# ControlBoard.net
KiCad netlist of a schematic drawn in Altium Designer
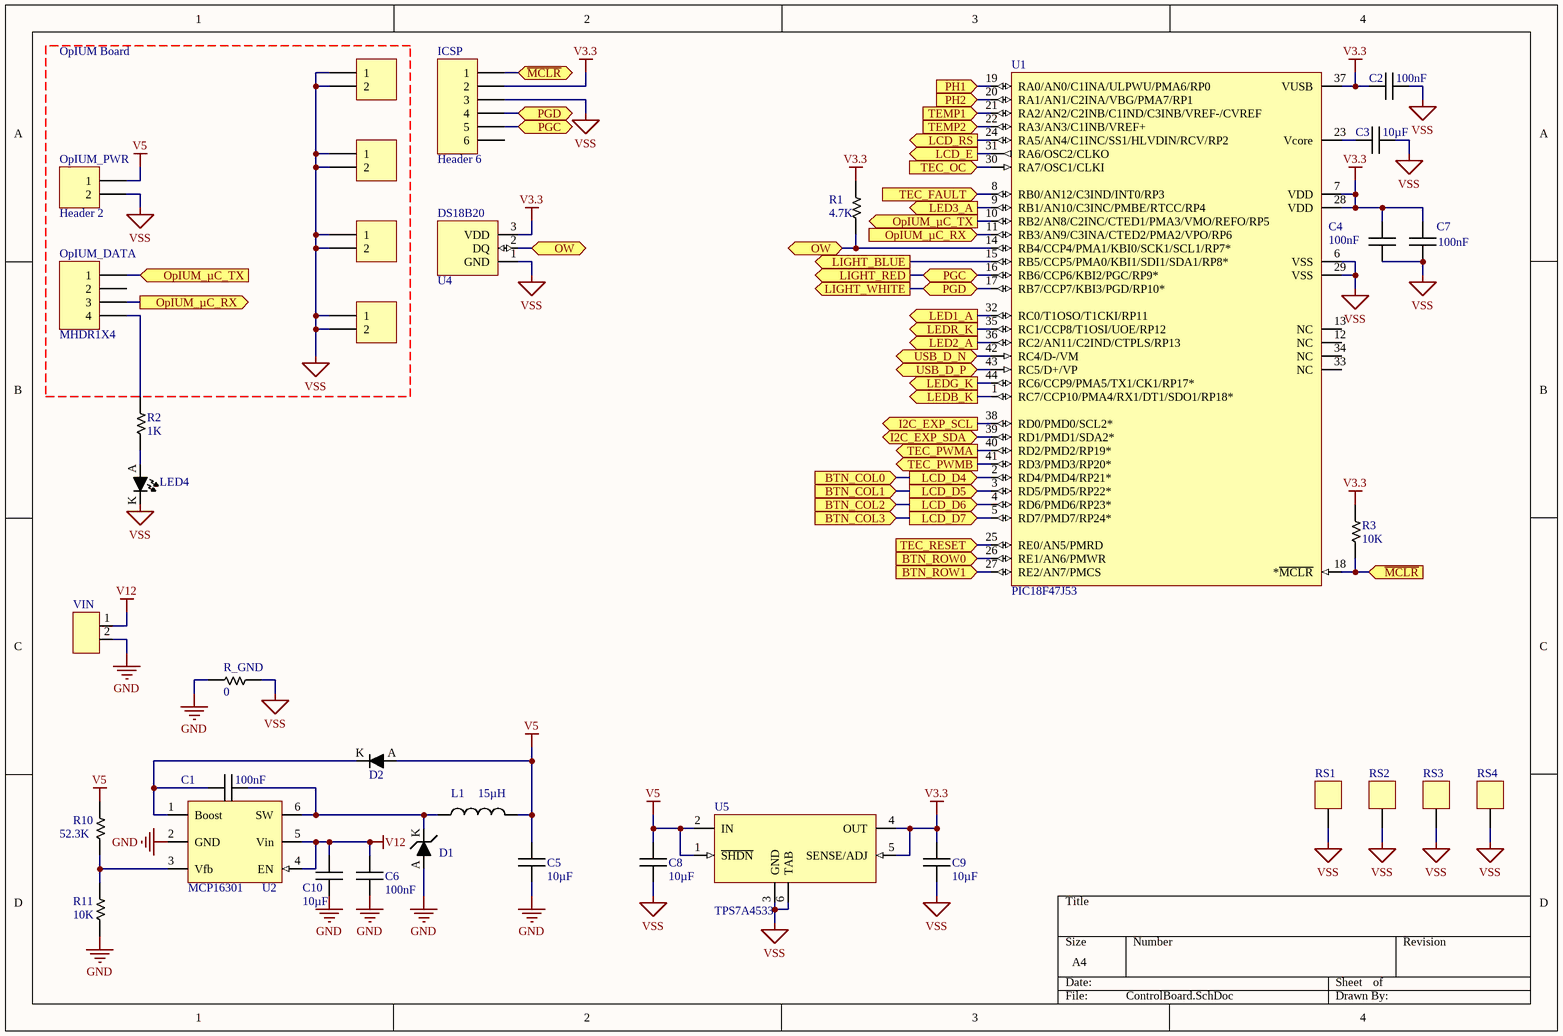
[diagram p0: ControlBoard.SchDoc]

(export (version "E")
  (design (tool "Eeschema 10.0.6"))
  (components
    (comp (ref "C1") (value "100nF") (footprint "CAPC1608N") (libsource (lib "Megaxone") (part "Capacitor")))
    (comp (ref "C2") (value "100nF") (footprint "CAPC1608N") (libsource (lib "Megaxone") (part "Capacitor")))
    (comp (ref "C3") (value "10µF") (footprint "CAPC2012N") (libsource (lib "Megaxone") (part "Capacitor")))
    (comp (ref "C4") (value "100nF") (footprint "CAPC1608N") (libsource (lib "Megaxone") (part "Capacitor")))
    (comp (ref "C5") (value "10µF") (footprint "CAPC2012N") (libsource (lib "Megaxone") (part "Capacitor")))
    (comp (ref "C6") (value "100nF") (footprint "CAPC1608N") (libsource (lib "Megaxone") (part "Capacitor")))
    (comp (ref "C7") (value "100nF") (footprint "CAPC1608N") (libsource (lib "Megaxone") (part "Capacitor")))
    (comp (ref "C8") (value "10µF") (footprint "CAPC2012N") (libsource (lib "Megaxone") (part "Capacitor")))
    (comp (ref "C9") (value "10µF") (footprint "CAPC2012N") (libsource (lib "Megaxone") (part "Capacitor")))
    (comp (ref "C10") (value "10µF") (footprint "CAPC3225N") (libsource (lib "Megaxone") (part "Capacitor")))
    (comp (ref "D1")
      (value "Schottky Diode")
      (footprint "DO-214AC")
      (libsource (lib "Megaxone") (part "Schottky Diode"))
    )
    (comp (ref "D2") (value "Diode") (footprint "SOT323") (libsource (lib "Megaxone") (part "Diode")))
    (comp (ref "ICSP")
      (value "Header 6")
      (footprint "HDR1X6")
      (description "Header, 6-Pin")
      (fields (field (name "PUBLISHER") "Altium Limited"))
      (libsource (lib "Miscellaneous Connectors") (part "Header 6"))
    )
    (comp (ref "L1")
      (value "15µH")
      (footprint "INDUCTOR 6×6mm Taiyo Yuden")
      (libsource (lib "Megaxone") (part "Inductor"))
    )
    (comp (ref "LED4") (value "~") (footprint "LED 1608m") (libsource (lib "Megaxone") (part "LED")))
    (comp (ref "OpIUM_DATA")
      (value "MHDR1X4")
      (footprint "MHDR1X4")
      (description "Header, 4-Pin")
      (fields (field (name "PUBLISHER") "Altium Limited"))
      (libsource (lib "Miscellaneous Connectors") (part "MHDR1X4"))
    )
    (comp (ref "OpIUM_PWR")
      (value "Header 2")
      (footprint "HDR1X2")
      (description "Header, 2-Pin")
      (fields (field (name "PUBLISHER") "Altium Limited"))
      (libsource (lib "Miscellaneous Connectors") (part "Header 2"))
    )
    (comp (ref "R1") (value "4.7K") (footprint "RESC1608N") (libsource (lib "Megaxone") (part "Resistor")))
    (comp (ref "R2") (value "1K") (footprint "RESC1608N") (libsource (lib "Megaxone") (part "Resistor")))
    (comp (ref "R3") (value "10K") (footprint "RESC1608N") (libsource (lib "Megaxone") (part "Resistor")))
    (comp (ref "R10") (value "52.3K") (footprint "RESC1608N") (libsource (lib "Megaxone") (part "Resistor")))
    (comp (ref "R11") (value "10K") (footprint "RESC1608N") (libsource (lib "Megaxone") (part "Resistor")))
    (comp (ref "RS1")
      (value "PCB Riser")
      (footprint "PCB Riser 6×10mm 3mm")
      (libsource (lib "Megaxone") (part "PCB Riser"))
    )
    (comp (ref "RS2")
      (value "PCB Riser")
      (footprint "PCB Riser 6×10mm 3mm")
      (libsource (lib "Megaxone") (part "PCB Riser"))
    )
    (comp (ref "RS3")
      (value "PCB Riser")
      (footprint "PCB Riser 6×10mm 3mm")
      (libsource (lib "Megaxone") (part "PCB Riser"))
    )
    (comp (ref "RS4")
      (value "PCB Riser")
      (footprint "PCB Riser 6×10mm 3mm")
      (libsource (lib "Megaxone") (part "PCB Riser"))
    )
    (comp (ref "R_GND") (value "0") (footprint "RESC1608N") (libsource (lib "") (part "Resistor_1")))
    (comp (ref "SUPPORT1")
      (value "MHDR1X2")
      (footprint "MHDR1X2")
      (description "Header, 2-Pin")
      (fields (field (name "PUBLISHER") "Altium Limited"))
      (libsource (lib "Miscellaneous Connectors") (part "MHDR1X2"))
    )
    (comp (ref "SUPPORT2")
      (value "MHDR1X2")
      (footprint "MHDR1X2")
      (description "Header, 2-Pin")
      (fields (field (name "PUBLISHER") "Altium Limited"))
      (libsource (lib "Miscellaneous Connectors") (part "MHDR1X2"))
    )
    (comp (ref "SUPPORT3")
      (value "MHDR1X2")
      (footprint "MHDR1X2")
      (description "Header, 2-Pin")
      (fields (field (name "PUBLISHER") "Altium Limited"))
      (libsource (lib "Miscellaneous Connectors") (part "MHDR1X2"))
    )
    (comp (ref "SUPPORT4")
      (value "MHDR1X2")
      (footprint "MHDR1X2")
      (description "Header, 2-Pin")
      (fields (field (name "PUBLISHER") "Altium Limited"))
      (libsource (lib "Miscellaneous Connectors") (part "MHDR1X2"))
    )
    (comp (ref "U1")
      (value "PIC18F47J53")
      (footprint "TQFP-PT44_N")
      (libsource (lib "Megaxone") (part "PIC18F47J53"))
    )
    (comp (ref "U2")
      (value "MCP16301")
      (footprint "SOT23-6_N")
      (libsource (lib "Megaxone") (part "MCP16301"))
    )
    (comp (ref "U4") (value "DS18B20") (footprint "TO-92A") (libsource (lib "Megaxone") (part "DS18B20")))
    (comp (ref "U5")
      (value "TPS7A4533")
      (footprint "SOT223-6N")
      (libsource (lib "Megaxone") (part "TPS7A45xx"))
    )
    (comp (ref "VIN")
      (value "High-Power Connector 2p")
      (footprint "High-Power Connector 2")
      (libsource (lib "Megaxone") (part "High-Power Connector 2p"))
    )
  )
  (nets
    (net (code "1") (name "/BTN_COL0") (class "Default")
      (node (ref "U1") (pin "2") (pinfunction "RD4/PMD4/RP21*_2") (pintype "bidirectional"))
    )
    (net (code "2") (name "/BTN_COL1") (class "Default")
      (node (ref "U1") (pin "3") (pinfunction "RD5/PMD5/RP22*_3") (pintype "bidirectional"))
    )
    (net (code "3") (name "/BTN_COL2") (class "Default")
      (node (ref "U1") (pin "4") (pinfunction "RD6/PMD6/RP23*_4") (pintype "bidirectional"))
    )
    (net (code "4") (name "/BTN_COL3") (class "Default")
      (node (ref "U1") (pin "5") (pinfunction "RD7/PMD7/RP24*_5") (pintype "bidirectional"))
    )
    (net (code "5") (name "/BTN_ROW0") (class "Default")
      (node (ref "U1") (pin "26") (pinfunction "RE1/AN6/PMWR_26") (pintype "bidirectional"))
    )
    (net (code "6") (name "/BTN_ROW1") (class "Default")
      (node (ref "U1") (pin "27") (pinfunction "RE2/AN7/PMCS_27") (pintype "bidirectional"))
    )
    (net (code "7") (name "/I2C_EXP_SCL") (class "Default")
      (node (ref "U1") (pin "38") (pinfunction "RD0/PMD0/SCL2*_38") (pintype "bidirectional"))
    )
    (net (code "8") (name "/I2C_EXP_SDA") (class "Default")
      (node (ref "U1") (pin "39") (pinfunction "RD1/PMD1/SDA2*_39") (pintype "bidirectional"))
    )
    (net (code "9") (name "/LCD_E") (class "Default")
      (node (ref "U1") (pin "31") (pinfunction "RA6/OSC2/CLKO_31") (pintype "output"))
    )
    (net (code "10") (name "/LCD_RS") (class "Default")
      (node (ref "U1") (pin "24") (pinfunction "RA5/AN4/C1INC/SS1/HLVDIN/RCV/RP2_24") (pintype "bidirectional"))
    )
    (net (code "11") (name "/LED1_A") (class "Default")
      (node (ref "U1") (pin "32") (pinfunction "RC0/T1OSO/T1CKI/RP11_32") (pintype "bidirectional"))
    )
    (net (code "12") (name "/LED2_A") (class "Default")
      (node (ref "U1") (pin "36") (pinfunction "RC2/AN11/C2IND/CTPLS/RP13_36") (pintype "bidirectional"))
    )
    (net (code "13") (name "/LED3_A") (class "Default")
      (node (ref "U1") (pin "9") (pinfunction "RB1/AN10/C3INC/PMBE/RTCC/RP4_9") (pintype "bidirectional"))
    )
    (net (code "14") (name "/LEDB_K") (class "Default")
      (node (ref "U1") (pin "1") (pinfunction "RC7/CCP10/PMA4/RX1/DT1/SDO1/RP18*_1") (pintype "bidirectional"))
    )
    (net (code "15") (name "/LEDG_K") (class "Default")
      (node (ref "U1") (pin "44") (pinfunction "RC6/CCP9/PMA5/TX1/CK1/RP17*_44") (pintype "bidirectional"))
    )
    (net (code "16") (name "/LEDR_K") (class "Default")
      (node (ref "U1") (pin "35") (pinfunction "RC1/CCP8/T1OSI/UOE/RP12_35") (pintype "bidirectional"))
    )
    (net (code "17") (name "/LIGHT_BLUE") (class "Default")
      (node (ref "U1") (pin "15") (pinfunction "RB5/CCP5/PMA0/KBI1/SDI1/SDA1/RP8*_15") (pintype "bidirectional"))
    )
    (net (code "18") (name "/LIGHT_RED") (class "Default")
      (node (ref "ICSP") (pin "5") (pinfunction "5_5") (pintype "passive"))
      (node (ref "U1") (pin "16") (pinfunction "RB6/CCP6/KBI2/PGC/RP9*_16") (pintype "bidirectional"))
    )
    (net (code "19") (name "/LIGHT_WHITE") (class "Default")
      (node (ref "ICSP") (pin "4") (pinfunction "4_4") (pintype "passive"))
      (node (ref "U1") (pin "17") (pinfunction "RB7/CCP7/KBI3/PGD/RP10*_17") (pintype "bidirectional"))
    )
    (net (code "20") (name "/OW") (class "Default")
      (node (ref "R1") (pin "1") (pinfunction "1_1") (pintype "passive"))
      (node (ref "U1") (pin "14") (pinfunction "RB4/CCP4/PMA1/KBI0/SCK1/SCL1/RP7*_14") (pintype "bidirectional"))
      (node (ref "U4") (pin "2") (pinfunction "DQ_2") (pintype "bidirectional"))
    )
    (net (code "21") (name "/OpIUM_µC_RX") (class "Default")
      (node (ref "OpIUM_DATA") (pin "3") (pinfunction "3_3") (pintype "passive"))
      (node (ref "U1") (pin "11") (pinfunction "RB3/AN9/C3INA/CTED2/PMA2/VPO/RP6_11") (pintype "bidirectional"))
    )
    (net (code "22") (name "/OpIUM_µC_TX") (class "Default")
      (node (ref "OpIUM_DATA") (pin "1") (pinfunction "1_1") (pintype "passive"))
      (node (ref "U1") (pin "10") (pinfunction "RB2/AN8/C2INC/CTED1/PMA3/VMO/REFO/RP5_10") (pintype "bidirectional"))
    )
    (net (code "23") (name "/PH1") (class "Default")
      (node (ref "U1") (pin "19") (pinfunction "RA0/AN0/C1INA/ULPWU/PMA6/RP0_19") (pintype "bidirectional"))
    )
    (net (code "24") (name "/PH2") (class "Default")
      (node (ref "U1") (pin "20") (pinfunction "RA1/AN1/C2INA/VBG/PMA7/RP1_20") (pintype "bidirectional"))
    )
    (net (code "25") (name "/TEC_FAULT") (class "Default")
      (node (ref "U1") (pin "8") (pinfunction "RB0/AN12/C3IND/INT0/RP3_8") (pintype "bidirectional"))
    )
    (net (code "26") (name "/TEC_OC") (class "Default")
      (node (ref "U1") (pin "30") (pinfunction "RA7/OSC1/CLKI_30") (pintype "input"))
    )
    (net (code "27") (name "/TEC_PWMA") (class "Default")
      (node (ref "U1") (pin "40") (pinfunction "RD2/PMD2/RP19*_40") (pintype "bidirectional"))
    )
    (net (code "28") (name "/TEC_PWMB") (class "Default")
      (node (ref "U1") (pin "41") (pinfunction "RD3/PMD3/RP20*_41") (pintype "bidirectional"))
    )
    (net (code "29") (name "/TEC_RESET") (class "Default")
      (node (ref "U1") (pin "25") (pinfunction "RE0/AN5/PMRD_25") (pintype "bidirectional"))
    )
    (net (code "30") (name "/TEMP1") (class "Default")
      (node (ref "U1") (pin "21") (pinfunction "RA2/AN2/C2INB/C1IND/C3INB/VREF-/CVREF_21") (pintype "bidirectional"))
    )
    (net (code "31") (name "/TEMP2") (class "Default")
      (node (ref "U1") (pin "22") (pinfunction "RA3/AN3/C1INB/VREF+_22") (pintype "bidirectional"))
    )
    (net (code "32") (name "/USB_D_N") (class "Default")
      (node (ref "U1") (pin "42") (pinfunction "RC4/D-/VM_42") (pintype "input"))
    )
    (net (code "33") (name "/USB_D_P") (class "Default")
      (node (ref "U1") (pin "43") (pinfunction "RC5/D+/VP_43") (pintype "input"))
    )
    (net (code "34") (name "/~{MCLR}") (class "Default")
      (node (ref "ICSP") (pin "1") (pinfunction "1_1") (pintype "passive"))
      (node (ref "R3") (pin "1") (pinfunction "1_1") (pintype "passive"))
      (node (ref "U1") (pin "18") (pinfunction "*~{MCLR}_18") (pintype "input"))
    )
    (net (code "35") (name "GND") (class "Default")
      (node (ref "C10") (pin "1") (pinfunction "1_1") (pintype "passive"))
      (node (ref "C5") (pin "1") (pinfunction "1_1") (pintype "passive"))
      (node (ref "C6") (pin "2") (pinfunction "2_2") (pintype "passive"))
      (node (ref "D1") (pin "A") (pinfunction "Anode_A") (pintype "power_in"))
      (node (ref "R11") (pin "1") (pinfunction "1_1") (pintype "passive"))
      (node (ref "R_GND") (pin "1") (pinfunction "1_1") (pintype "passive"))
      (node (ref "U2") (pin "2") (pinfunction "GND_2") (pintype "power_in"))
      (node (ref "VIN") (pin "2") (pinfunction "2_2") (pintype "power_in"))
    )
    (net (code "36") (name "Net-(D1-Kathode)") (class "Default")
      (node (ref "C1") (pin "1") (pinfunction "1_1") (pintype "passive"))
      (node (ref "D1") (pin "K") (pinfunction "Kathode_K") (pintype "power_in"))
      (node (ref "L1") (pin "1") (pinfunction "1_1") (pintype "passive"))
      (node (ref "U2") (pin "6") (pinfunction "SW_6") (pintype "power_in"))
    )
    (net (code "37") (name "Net-(LED4-PadA)") (class "Default")
      (node (ref "LED4") (pin "A") (pinfunction "A_A") (pintype "passive"))
      (node (ref "R2") (pin "1") (pinfunction "1_1") (pintype "passive"))
    )
    (net (code "38") (name "Net-(OpIUM_DATA-Pad4)") (class "Default")
      (node (ref "OpIUM_DATA") (pin "4") (pinfunction "4_4") (pintype "passive"))
      (node (ref "R2") (pin "2") (pinfunction "2_2") (pintype "passive"))
    )
    (net (code "39") (name "Net-(U1-Vcore)") (class "Default")
      (node (ref "C3") (pin "2") (pinfunction "2_2") (pintype "passive"))
      (node (ref "U1") (pin "23") (pinfunction "Vcore_23") (pintype "power_in"))
    )
    (net (code "40") (name "Net-(U2-Boost)") (class "Default")
      (node (ref "C1") (pin "2") (pinfunction "2_2") (pintype "passive"))
      (node (ref "D2") (pin "K") (pinfunction "K_K") (pintype "power_in"))
      (node (ref "U2") (pin "1") (pinfunction "Boost_1") (pintype "passive"))
    )
    (net (code "41") (name "Net-(U2-Vfb)") (class "Default")
      (node (ref "R10") (pin "1") (pinfunction "1_1") (pintype "passive"))
      (node (ref "R11") (pin "2") (pinfunction "2_2") (pintype "passive"))
      (node (ref "U2") (pin "3") (pinfunction "Vfb_3") (pintype "passive"))
    )
    (net (code "42") (name "V3.3") (class "Default")
      (node (ref "C2") (pin "2") (pinfunction "2_2") (pintype "passive"))
      (node (ref "C4") (pin "2") (pinfunction "2_2") (pintype "passive"))
      (node (ref "C7") (pin "2") (pinfunction "2_2") (pintype "passive"))
      (node (ref "C9") (pin "2") (pinfunction "2_2") (pintype "passive"))
      (node (ref "ICSP") (pin "2") (pinfunction "2_2") (pintype "passive"))
      (node (ref "R1") (pin "2") (pinfunction "2_2") (pintype "passive"))
      (node (ref "R3") (pin "2") (pinfunction "2_2") (pintype "passive"))
      (node (ref "U1") (pin "28") (pinfunction "VDD_28") (pintype "power_in"))
      (node (ref "U1") (pin "37") (pinfunction "VUSB_37") (pintype "power_in"))
      (node (ref "U1") (pin "7") (pinfunction "VDD_7") (pintype "power_in"))
      (node (ref "U4") (pin "3") (pinfunction "VDD_3") (pintype "power_in"))
      (node (ref "U5") (pin "4") (pinfunction "OUT_4") (pintype "power_in"))
      (node (ref "U5") (pin "5") (pinfunction "SENSE/ADJ_5") (pintype "input"))
    )
    (net (code "43") (name "V5") (class "Default")
      (node (ref "C5") (pin "2") (pinfunction "2_2") (pintype "passive"))
      (node (ref "C8") (pin "2") (pinfunction "2_2") (pintype "passive"))
      (node (ref "D2") (pin "A") (pinfunction "A_A") (pintype "power_in"))
      (node (ref "L1") (pin "2") (pinfunction "2_2") (pintype "passive"))
      (node (ref "OpIUM_PWR") (pin "1") (pinfunction "1_1") (pintype "passive"))
      (node (ref "R10") (pin "2") (pinfunction "2_2") (pintype "passive"))
      (node (ref "U5") (pin "1") (pinfunction "~{SHDN}_1") (pintype "input"))
      (node (ref "U5") (pin "2") (pinfunction "IN_2") (pintype "power_in"))
    )
    (net (code "44") (name "V12") (class "Default")
      (node (ref "C10") (pin "2") (pinfunction "2_2") (pintype "passive"))
      (node (ref "C6") (pin "1") (pinfunction "1_1") (pintype "passive"))
      (node (ref "U2") (pin "4") (pinfunction "EN_4") (pintype "input"))
      (node (ref "U2") (pin "5") (pinfunction "Vin_5") (pintype "power_in"))
      (node (ref "VIN") (pin "1") (pinfunction "1_1") (pintype "power_in"))
    )
    (net (code "45") (name "VSS") (class "Default")
      (node (ref "C2") (pin "1") (pinfunction "1_1") (pintype "passive"))
      (node (ref "C3") (pin "1") (pinfunction "1_1") (pintype "passive"))
      (node (ref "C4") (pin "1") (pinfunction "1_1") (pintype "passive"))
      (node (ref "C7") (pin "1") (pinfunction "1_1") (pintype "passive"))
      (node (ref "C8") (pin "1") (pinfunction "1_1") (pintype "passive"))
      (node (ref "C9") (pin "1") (pinfunction "1_1") (pintype "passive"))
      (node (ref "ICSP") (pin "3") (pinfunction "3_3") (pintype "passive"))
      (node (ref "LED4") (pin "K") (pinfunction "K_K") (pintype "passive"))
      (node (ref "OpIUM_PWR") (pin "2") (pinfunction "2_2") (pintype "passive"))
      (node (ref "RS1") (pin "1") (pinfunction "1_1") (pintype "power_in"))
      (node (ref "RS2") (pin "1") (pinfunction "1_1") (pintype "power_in"))
      (node (ref "RS3") (pin "1") (pinfunction "1_1") (pintype "power_in"))
      (node (ref "RS4") (pin "1") (pinfunction "1_1") (pintype "power_in"))
      (node (ref "R_GND") (pin "2") (pinfunction "2_2") (pintype "passive"))
      (node (ref "SUPPORT1") (pin "1") (pinfunction "1_1") (pintype "passive"))
      (node (ref "SUPPORT1") (pin "2") (pinfunction "2_2") (pintype "passive"))
      (node (ref "SUPPORT2") (pin "1") (pinfunction "1_1") (pintype "passive"))
      (node (ref "SUPPORT2") (pin "2") (pinfunction "2_2") (pintype "passive"))
      (node (ref "SUPPORT3") (pin "1") (pinfunction "1_1") (pintype "passive"))
      (node (ref "SUPPORT3") (pin "2") (pinfunction "2_2") (pintype "passive"))
      (node (ref "SUPPORT4") (pin "1") (pinfunction "1_1") (pintype "passive"))
      (node (ref "SUPPORT4") (pin "2") (pinfunction "2_2") (pintype "passive"))
      (node (ref "U1") (pin "29") (pinfunction "VSS_29") (pintype "power_in"))
      (node (ref "U1") (pin "6") (pinfunction "VSS_6") (pintype "power_in"))
      (node (ref "U4") (pin "1") (pinfunction "GND_1") (pintype "power_in"))
      (node (ref "U5") (pin "3") (pinfunction "GND_3") (pintype "power_in"))
      (node (ref "U5") (pin "6") (pinfunction "TAB_6") (pintype "power_in"))
    )
    (net (code "46") (name "unconnected-(ICSP-Pad6)") (class "Default")
      (node (ref "ICSP") (pin "6") (pinfunction "6_6") (pintype "passive"))
    )
    (net (code "47") (name "unconnected-(OpIUM_DATA-Pad2)") (class "Default")
      (node (ref "OpIUM_DATA") (pin "2") (pinfunction "2_2") (pintype "passive"))
    )
    (net (code "48") (name "unconnected-(U1-NC-Pad12)") (class "Default")
      (node (ref "U1") (pin "12") (pinfunction "NC_12") (pintype "passive"))
    )
    (net (code "49") (name "unconnected-(U1-NC-Pad13)") (class "Default")
      (node (ref "U1") (pin "13") (pinfunction "NC_13") (pintype "passive"))
    )
    (net (code "50") (name "unconnected-(U1-NC-Pad33)") (class "Default")
      (node (ref "U1") (pin "33") (pinfunction "NC_33") (pintype "passive"))
    )
    (net (code "51") (name "unconnected-(U1-NC-Pad34)") (class "Default")
      (node (ref "U1") (pin "34") (pinfunction "NC_34") (pintype "passive"))
    )
  )
)
